# trx-mainboard.net
KiCad netlist of a schematic drawn in EAGLE
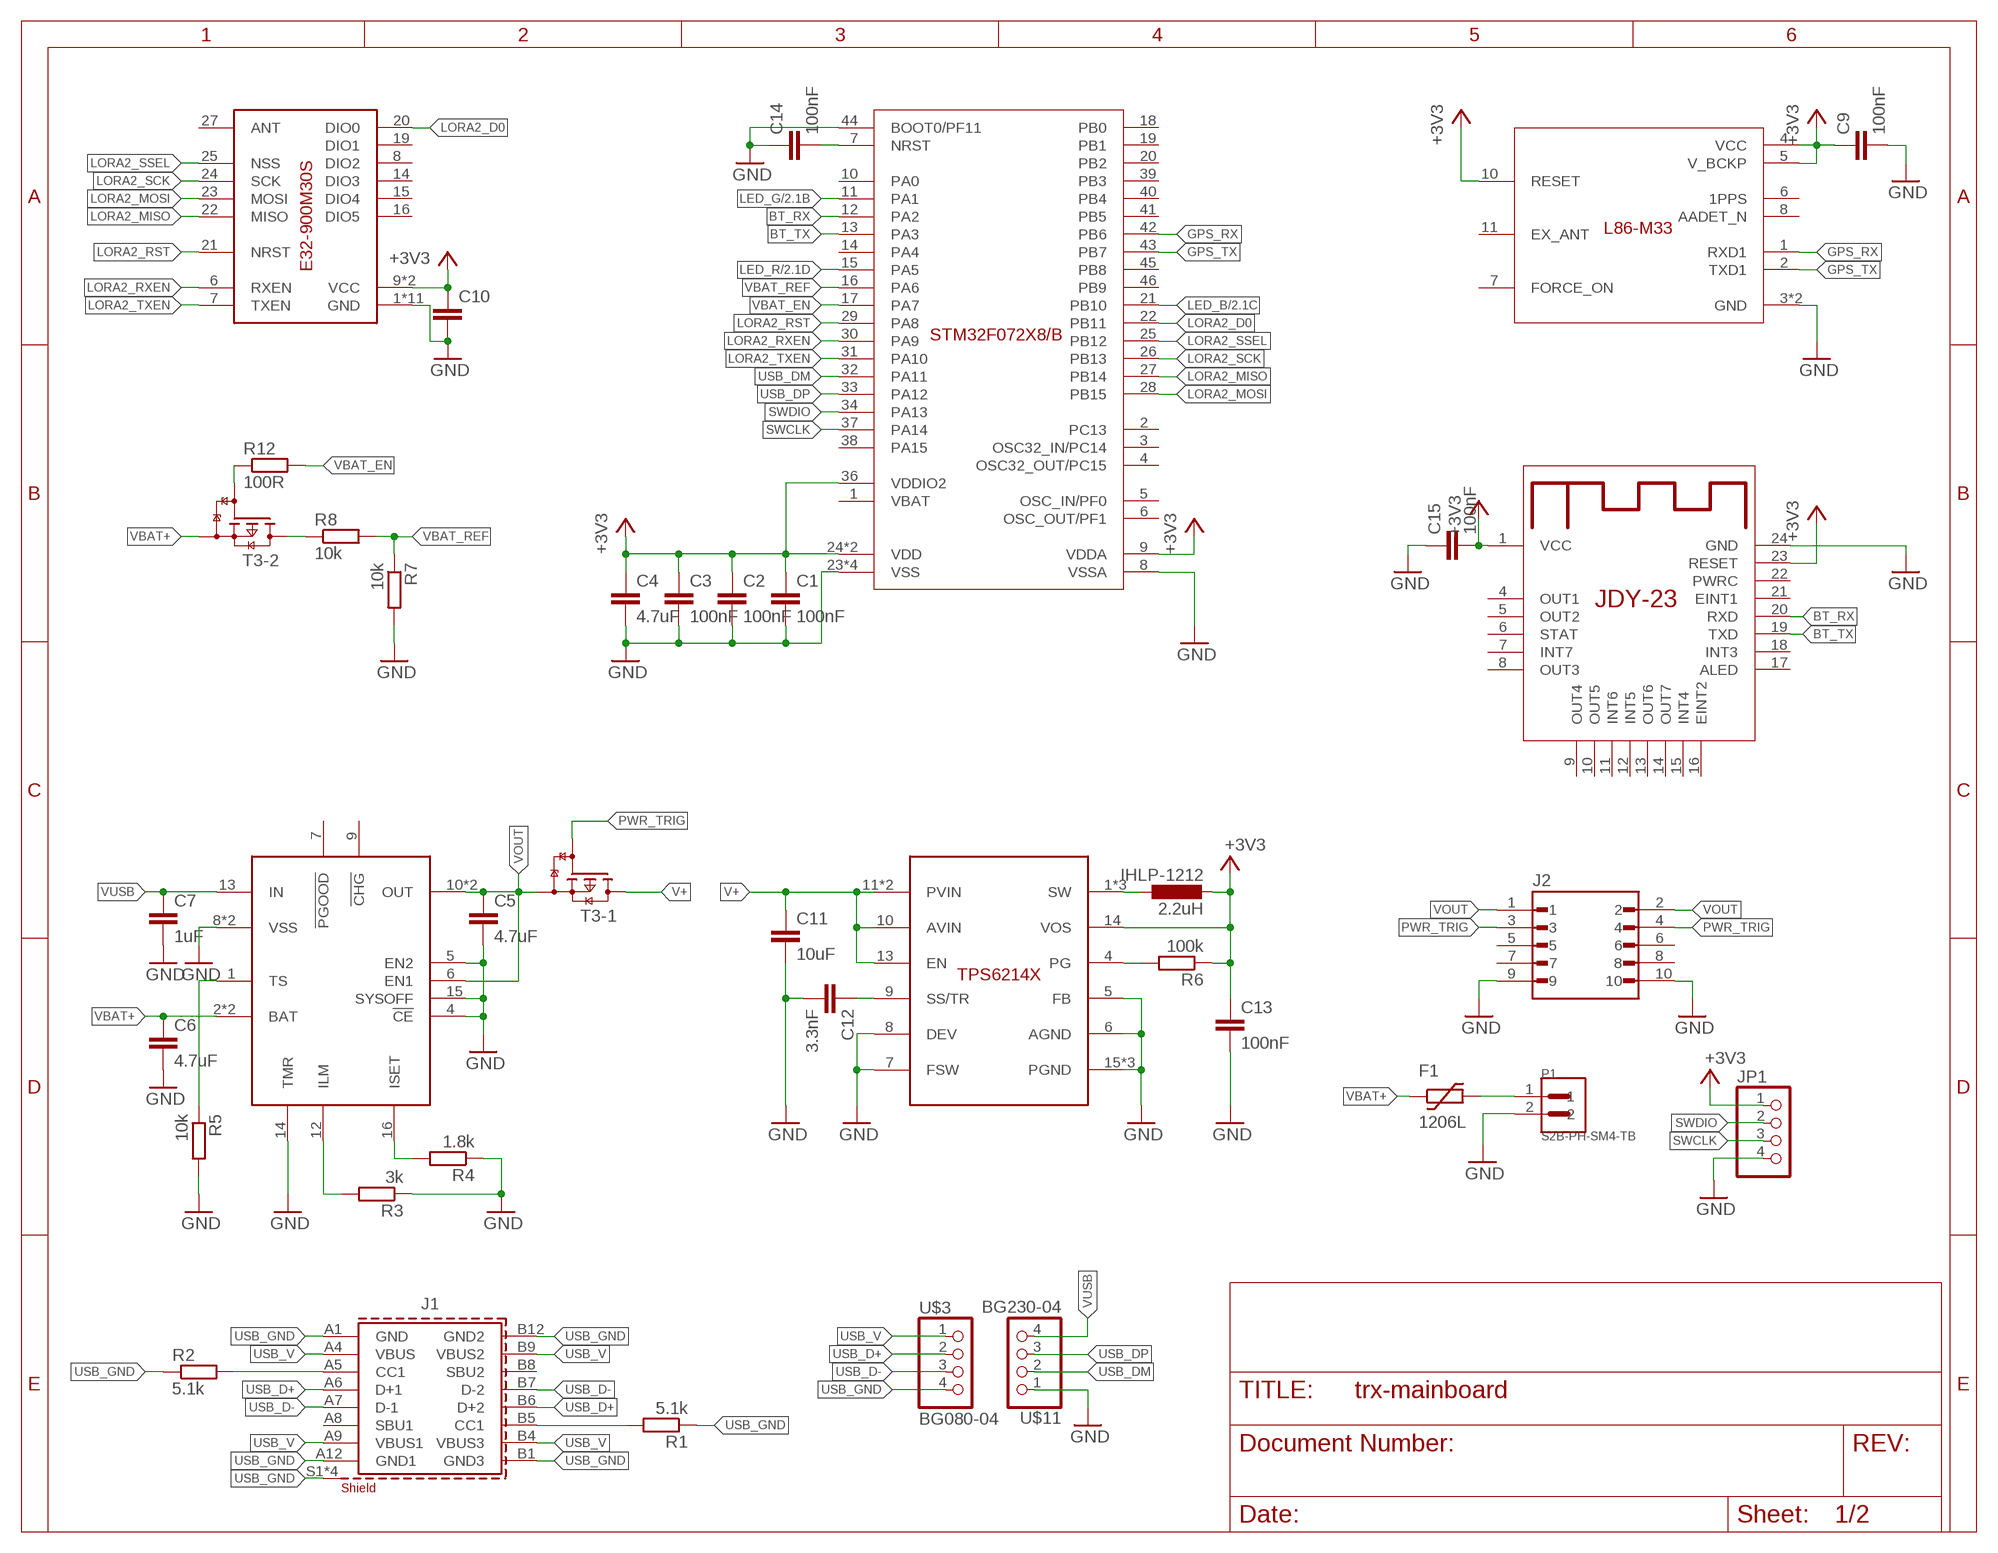
[diagram p0: schematic, sheet 1]
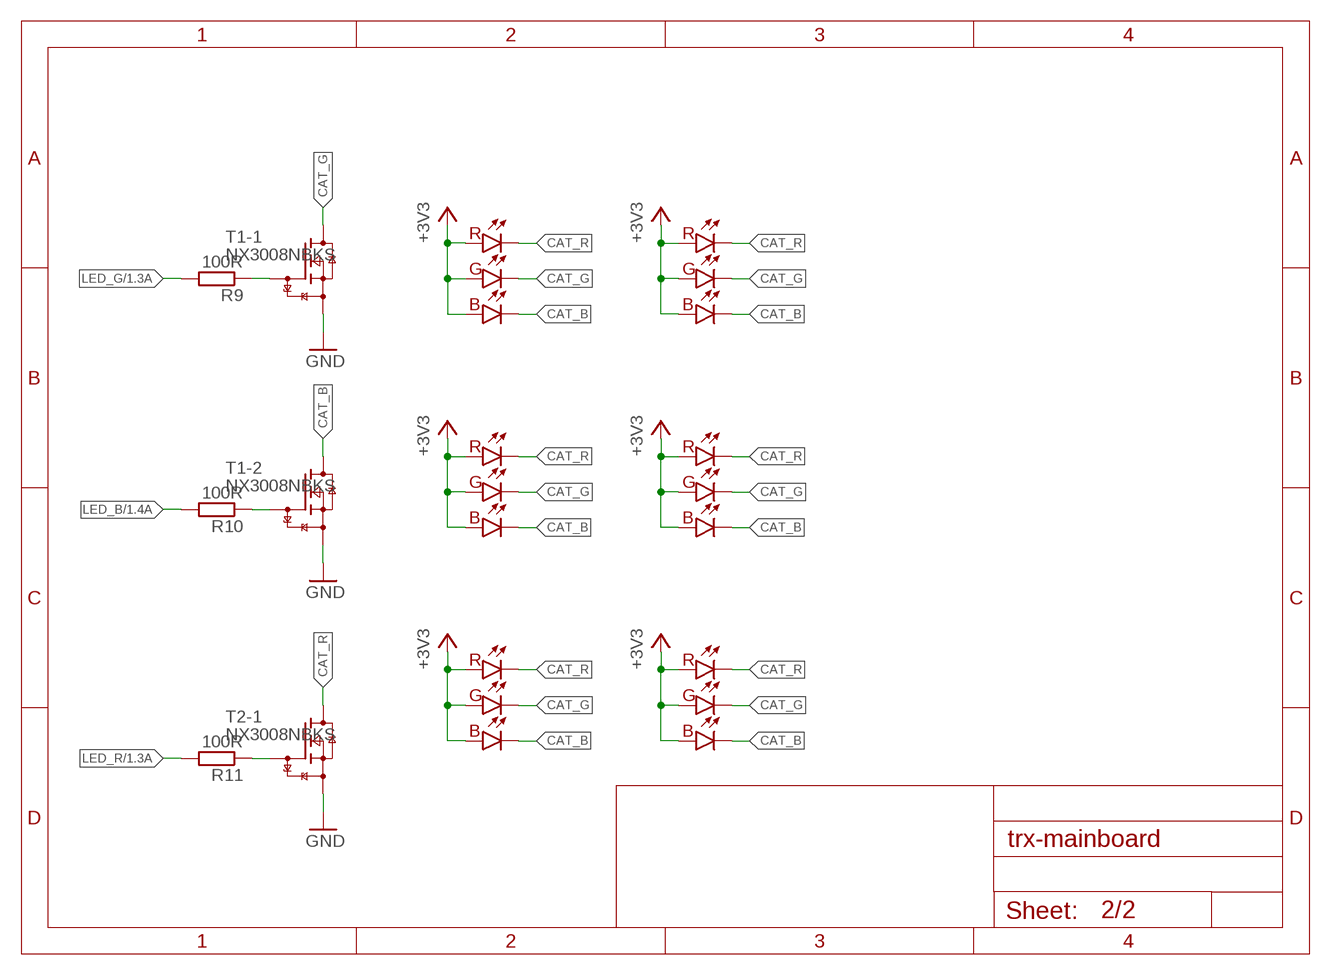
[diagram p1: schematic, sheet 2]

(export (version "E")
  (design (tool "Eeschema 10.0.6"))
  (components
    (comp (ref "C1")
      (value "100nF")
      (footprint "eagle-import:C0805")
      (libsource (lib "eagle-import") (part "C-EUC0805"))
    )
    (comp (ref "C2")
      (value "100nF")
      (footprint "eagle-import:C0805")
      (libsource (lib "eagle-import") (part "C-EUC0805"))
    )
    (comp (ref "C3")
      (value "100nF")
      (footprint "eagle-import:C0805")
      (libsource (lib "eagle-import") (part "C-EUC0805"))
    )
    (comp (ref "C4")
      (value "4.7uF")
      (footprint "eagle-import:C0805")
      (libsource (lib "eagle-import") (part "C-EUC0805"))
    )
    (comp (ref "C5")
      (value "4.7uF")
      (footprint "eagle-import:C0805")
      (libsource (lib "eagle-import") (part "C-EUC0805"))
    )
    (comp (ref "C6")
      (value "4.7uF")
      (footprint "eagle-import:C0805")
      (libsource (lib "eagle-import") (part "C-EUC0805"))
    )
    (comp (ref "C7")
      (value "1uF")
      (footprint "eagle-import:C0805")
      (libsource (lib "eagle-import") (part "C-EUC0805"))
    )
    (comp (ref "C9")
      (value "100nF")
      (footprint "eagle-import:C0805")
      (libsource (lib "eagle-import") (part "C-EUC0805"))
    )
    (comp (ref "C10")
      (value "4.7uF")
      (footprint "eagle-import:C0805")
      (libsource (lib "eagle-import") (part "C-EUC0805"))
    )
    (comp (ref "C11")
      (value "10uF")
      (footprint "eagle-import:C0805")
      (libsource (lib "eagle-import") (part "C-EUC0805"))
    )
    (comp (ref "C12")
      (value "3.3nF")
      (footprint "eagle-import:C0805")
      (libsource (lib "eagle-import") (part "C-EUC0805"))
    )
    (comp (ref "C13")
      (value "100nF")
      (footprint "eagle-import:C0805")
      (libsource (lib "eagle-import") (part "C-EUC0805"))
    )
    (comp (ref "C14")
      (value "100nF")
      (footprint "eagle-import:C0805")
      (libsource (lib "eagle-import") (part "C-EUC0805"))
    )
    (comp (ref "C15")
      (value "100nF")
      (footprint "eagle-import:C0805")
      (libsource (lib "eagle-import") (part "C-EUC0805"))
    )
    (comp (ref "F1")
      (value "1206L")
      (footprint "eagle-import:1206L")
      (libsource (lib "eagle-import") (part "1206L"))
    )
    (comp (ref "J1")
      (value "629722000214")
      (footprint "eagle-import:629722000214")
      (libsource (lib "eagle-import") (part "629722000214"))
    )
    (comp (ref "J2")
      (value "DF12NB(3.0)-10DP-0.5V")
      (footprint "eagle-import:HRS_DF12NB(3.0)-10DP-0.5V")
      (fields (field (name "MF") "Hirose") (field (name "MP") "DF12NB(3.0)-10DP-0.5V(51)"))
      (libsource (lib "eagle-import") (part "DF12NB(3.0)-10DP-0.5V"))
    )
    (comp (ref "JP1")
      (value "PINHD-1X04_2.54-SMD")
      (footprint "eagle-import:1X04SMD")
      (libsource (lib "eagle-import") (part "PINHD-1X04_2.54-SMD"))
    )
    (comp (ref "P1")
      (value "S2B-PH-SM4-TB")
      (footprint "eagle-import:JST_S2B-PH-SM4-TB")
      (fields (field (name "MF") "JST Sales"))
      (libsource (lib "eagle-import") (part "S2B-PH-SM4-TB"))
    )
    (comp (ref "R1")
      (value "5.1k")
      (footprint "eagle-import:R0805")
      (libsource (lib "eagle-import") (part "R-EU_R0805"))
    )
    (comp (ref "R2")
      (value "5.1k")
      (footprint "eagle-import:R0805")
      (libsource (lib "eagle-import") (part "R-EU_R0805"))
    )
    (comp (ref "R3")
      (value "3k")
      (footprint "eagle-import:R0805")
      (libsource (lib "eagle-import") (part "R-EU_R0805"))
    )
    (comp (ref "R4")
      (value "1.8k")
      (footprint "eagle-import:R0805")
      (libsource (lib "eagle-import") (part "R-EU_R0805"))
    )
    (comp (ref "R5")
      (value "10k")
      (footprint "eagle-import:R0805")
      (libsource (lib "eagle-import") (part "R-EU_R0805"))
    )
    (comp (ref "R6")
      (value "100k")
      (footprint "eagle-import:R0805")
      (libsource (lib "eagle-import") (part "R-EU_R0805"))
    )
    (comp (ref "R7")
      (value "10k")
      (footprint "eagle-import:R0805")
      (libsource (lib "eagle-import") (part "R-EU_R0805"))
    )
    (comp (ref "R8")
      (value "10k")
      (footprint "eagle-import:R0805")
      (libsource (lib "eagle-import") (part "R-EU_R0805"))
    )
    (comp (ref "R12")
      (value "100R")
      (footprint "eagle-import:R0805")
      (libsource (lib "eagle-import") (part "R-EU_R0805"))
    )
    (comp (ref "T3")
      (value "NX3008PBKS")
      (footprint "eagle-import:SOT363")
      (libsource (lib "eagle-import") (part "NX3008PBKS"))
    )
    (comp (ref "U$1")
      (value "L86-M33")
      (footprint "eagle-import:L86-M33")
      (libsource (lib "eagle-import") (part "L86-M33"))
    )
    (comp (ref "U$2")
      (value "TPS6214X")
      (footprint "eagle-import:VQFN16-3X3")
      (libsource (lib "eagle-import") (part "TPS6214X"))
    )
    (comp (ref "U$3")
      (value "BG080-04")
      (footprint "eagle-import:P-1X4_90-2.54X1.50MMX2.54MM-SMT")
      (libsource (lib "eagle-import") (part "BG080-04"))
    )
    (comp (ref "U$4")
      (value "IHLP-1212")
      (footprint "eagle-import:1212BZ")
      (libsource (lib "eagle-import") (part "IHLP-1212"))
    )
    (comp (ref "U$5")
      (value "JDY-23")
      (footprint "eagle-import:JDY-23")
      (libsource (lib "eagle-import") (part "JDY-23"))
    )
    (comp (ref "U$10")
      (value "STM32-F072X8/B-48")
      (footprint "eagle-import:UFQFPN48-7X7")
      (libsource (lib "eagle-import") (part "STM32-F072X8/B-48"))
    )
    (comp (ref "U$11")
      (value "BG230-04")
      (footprint "eagle-import:S-1X4_90-2.54MM-SMT")
      (libsource (lib "eagle-import") (part "BG230-04"))
    )
    (comp (ref "U$14")
      (value "E32-900M30S")
      (footprint "eagle-import:E32-900M30S")
      (libsource (lib "eagle-import") (part "E32-900M30S"))
    )
    (comp (ref "U2")
      (value "BQ2407X")
      (footprint "eagle-import:VQFN16-3X3")
      (libsource (lib "eagle-import") (part "BQ2407X"))
    )
    (comp (ref "R9")
      (value "100R")
      (footprint "eagle-import:R0805")
      (libsource (lib "eagle-import") (part "R-EU_R0805"))
    )
    (comp (ref "R10")
      (value "100R")
      (footprint "eagle-import:R0805")
      (libsource (lib "eagle-import") (part "R-EU_R0805"))
    )
    (comp (ref "R11")
      (value "100R")
      (footprint "eagle-import:R0805")
      (libsource (lib "eagle-import") (part "R-EU_R0805"))
    )
    (comp (ref "T1")
      (value "NX3008NBKS")
      (footprint "eagle-import:SOT363")
      (libsource (lib "eagle-import") (part "NX3008NBKS"))
    )
    (comp (ref "T2")
      (value "NX3008NBKS")
      (footprint "eagle-import:SOT363")
      (libsource (lib "eagle-import") (part "NX3008NBKS"))
    )
    (comp (ref "U$6")
      (value "RGB_LED")
      (footprint "eagle-import:PLCC6")
      (libsource (lib "eagle-import") (part "RGB_LED"))
    )
    (comp (ref "U$7")
      (value "RGB_LED")
      (footprint "eagle-import:PLCC6")
      (libsource (lib "eagle-import") (part "RGB_LED"))
    )
    (comp (ref "U$8")
      (value "RGB_LED")
      (footprint "eagle-import:PLCC6")
      (libsource (lib "eagle-import") (part "RGB_LED"))
    )
    (comp (ref "U$9")
      (value "RGB_LED")
      (footprint "eagle-import:PLCC6")
      (libsource (lib "eagle-import") (part "RGB_LED"))
    )
    (comp (ref "U$12")
      (value "RGB_LED")
      (footprint "eagle-import:PLCC6")
      (libsource (lib "eagle-import") (part "RGB_LED"))
    )
    (comp (ref "U$13")
      (value "RGB_LED")
      (footprint "eagle-import:PLCC6")
      (libsource (lib "eagle-import") (part "RGB_LED"))
    )
  )
  (nets
    (net (code "1") (name "+3V3") (class "Default")
      (node (ref "C1") (pin "1") (pinfunction "1_1") (pintype "passive"))
      (node (ref "C10") (pin "1") (pinfunction "1_1") (pintype "passive"))
      (node (ref "C13") (pin "1") (pinfunction "1_1") (pintype "passive"))
      (node (ref "C15") (pin "2") (pinfunction "2_2") (pintype "passive"))
      (node (ref "C2") (pin "1") (pinfunction "1_1") (pintype "passive"))
      (node (ref "C3") (pin "1") (pinfunction "1_1") (pintype "passive"))
      (node (ref "C4") (pin "1") (pinfunction "1_1") (pintype "passive"))
      (node (ref "C9") (pin "1") (pinfunction "1_1") (pintype "passive"))
      (node (ref "JP1") (pin "1") (pinfunction "1_1") (pintype "passive"))
      (node (ref "R6") (pin "1") (pinfunction "1_1") (pintype "passive"))
      (node (ref "U$1") (pin "10") (pinfunction "RESET_10") (pintype "bidirectional"))
      (node (ref "U$1") (pin "4") (pinfunction "VCC_4") (pintype "bidirectional"))
      (node (ref "U$1") (pin "5") (pinfunction "V_BCKP_5") (pintype "bidirectional"))
      (node (ref "U$10") (pin "24") (pinfunction "VDD_24") (pintype "bidirectional"))
      (node (ref "U$10") (pin "36") (pinfunction "VDDIO2_36") (pintype "bidirectional"))
      (node (ref "U$10") (pin "48") (pinfunction "VDD_48") (pintype "bidirectional"))
      (node (ref "U$10") (pin "9") (pinfunction "VDDA_9") (pintype "bidirectional"))
      (node (ref "U$12") (pin "1") (pinfunction "A.B_1") (pintype "passive"))
      (node (ref "U$12") (pin "3") (pinfunction "A.R_3") (pintype "passive"))
      (node (ref "U$12") (pin "5") (pinfunction "A.G_5") (pintype "passive"))
      (node (ref "U$13") (pin "1") (pinfunction "A.B_1") (pintype "passive"))
      (node (ref "U$13") (pin "3") (pinfunction "A.R_3") (pintype "passive"))
      (node (ref "U$13") (pin "5") (pinfunction "A.G_5") (pintype "passive"))
      (node (ref "U$14") (pin "10") (pinfunction "VCC_10") (pintype "bidirectional"))
      (node (ref "U$14") (pin "9") (pinfunction "VCC_9") (pintype "bidirectional"))
      (node (ref "U$2") (pin "14") (pinfunction "VOS_14") (pintype "bidirectional"))
      (node (ref "U$4") (pin "2") (pinfunction "2_2") (pintype "passive"))
      (node (ref "U$5") (pin "1") (pinfunction "VCC_1") (pintype "bidirectional"))
      (node (ref "U$5") (pin "23") (pinfunction "RESET_23") (pintype "bidirectional"))
      (node (ref "U$6") (pin "1") (pinfunction "A.B_1") (pintype "passive"))
      (node (ref "U$6") (pin "3") (pinfunction "A.R_3") (pintype "passive"))
      (node (ref "U$6") (pin "5") (pinfunction "A.G_5") (pintype "passive"))
      (node (ref "U$7") (pin "1") (pinfunction "A.B_1") (pintype "passive"))
      (node (ref "U$7") (pin "3") (pinfunction "A.R_3") (pintype "passive"))
      (node (ref "U$7") (pin "5") (pinfunction "A.G_5") (pintype "passive"))
      (node (ref "U$8") (pin "1") (pinfunction "A.B_1") (pintype "passive"))
      (node (ref "U$8") (pin "3") (pinfunction "A.R_3") (pintype "passive"))
      (node (ref "U$8") (pin "5") (pinfunction "A.G_5") (pintype "passive"))
      (node (ref "U$9") (pin "1") (pinfunction "A.B_1") (pintype "passive"))
      (node (ref "U$9") (pin "3") (pinfunction "A.R_3") (pintype "passive"))
      (node (ref "U$9") (pin "5") (pinfunction "A.G_5") (pintype "passive"))
    )
    (net (code "2") (name "BT_RX") (class "Default")
      (node (ref "U$10") (pin "12") (pinfunction "PA2_12") (pintype "bidirectional"))
      (node (ref "U$5") (pin "20") (pinfunction "RXD_20") (pintype "bidirectional"))
    )
    (net (code "3") (name "BT_TX") (class "Default")
      (node (ref "U$10") (pin "13") (pinfunction "PA3_13") (pintype "bidirectional"))
      (node (ref "U$5") (pin "19") (pinfunction "TXD_19") (pintype "bidirectional"))
    )
    (net (code "4") (name "CAT_B") (class "Default")
      (node (ref "T1") (pin "3") (pinfunction "D_3") (pintype "passive"))
      (node (ref "U$12") (pin "2") (pinfunction "C.B_2") (pintype "passive"))
      (node (ref "U$13") (pin "2") (pinfunction "C.B_2") (pintype "passive"))
      (node (ref "U$6") (pin "2") (pinfunction "C.B_2") (pintype "passive"))
      (node (ref "U$7") (pin "2") (pinfunction "C.B_2") (pintype "passive"))
      (node (ref "U$8") (pin "2") (pinfunction "C.B_2") (pintype "passive"))
      (node (ref "U$9") (pin "2") (pinfunction "C.B_2") (pintype "passive"))
    )
    (net (code "5") (name "CAT_G") (class "Default")
      (node (ref "T1") (pin "6") (pinfunction "D_6") (pintype "passive"))
      (node (ref "U$12") (pin "6") (pinfunction "C.G_6") (pintype "passive"))
      (node (ref "U$13") (pin "6") (pinfunction "C.G_6") (pintype "passive"))
      (node (ref "U$6") (pin "6") (pinfunction "C.G_6") (pintype "passive"))
      (node (ref "U$7") (pin "6") (pinfunction "C.G_6") (pintype "passive"))
      (node (ref "U$8") (pin "6") (pinfunction "C.G_6") (pintype "passive"))
      (node (ref "U$9") (pin "6") (pinfunction "C.G_6") (pintype "passive"))
    )
    (net (code "6") (name "CAT_R") (class "Default")
      (node (ref "T2") (pin "6") (pinfunction "D_6") (pintype "passive"))
      (node (ref "U$12") (pin "4") (pinfunction "C.R_4") (pintype "passive"))
      (node (ref "U$13") (pin "4") (pinfunction "C.R_4") (pintype "passive"))
      (node (ref "U$6") (pin "4") (pinfunction "C.R_4") (pintype "passive"))
      (node (ref "U$7") (pin "4") (pinfunction "C.R_4") (pintype "passive"))
      (node (ref "U$8") (pin "4") (pinfunction "C.R_4") (pintype "passive"))
      (node (ref "U$9") (pin "4") (pinfunction "C.R_4") (pintype "passive"))
    )
    (net (code "7") (name "GND") (class "Default")
      (node (ref "C1") (pin "2") (pinfunction "2_2") (pintype "passive"))
      (node (ref "C10") (pin "2") (pinfunction "2_2") (pintype "passive"))
      (node (ref "C11") (pin "2") (pinfunction "2_2") (pintype "passive"))
      (node (ref "C12") (pin "2") (pinfunction "2_2") (pintype "passive"))
      (node (ref "C13") (pin "2") (pinfunction "2_2") (pintype "passive"))
      (node (ref "C14") (pin "1") (pinfunction "1_1") (pintype "passive"))
      (node (ref "C15") (pin "1") (pinfunction "1_1") (pintype "passive"))
      (node (ref "C2") (pin "2") (pinfunction "2_2") (pintype "passive"))
      (node (ref "C3") (pin "2") (pinfunction "2_2") (pintype "passive"))
      (node (ref "C4") (pin "2") (pinfunction "2_2") (pintype "passive"))
      (node (ref "C5") (pin "2") (pinfunction "2_2") (pintype "passive"))
      (node (ref "C6") (pin "2") (pinfunction "2_2") (pintype "passive"))
      (node (ref "C7") (pin "2") (pinfunction "2_2") (pintype "passive"))
      (node (ref "C9") (pin "2") (pinfunction "2_2") (pintype "passive"))
      (node (ref "J2") (pin "10") (pinfunction "10_10") (pintype "passive"))
      (node (ref "J2") (pin "9") (pinfunction "9_9") (pintype "passive"))
      (node (ref "JP1") (pin "4") (pinfunction "4_4") (pintype "passive"))
      (node (ref "P1") (pin "2") (pinfunction "2_2") (pintype "passive"))
      (node (ref "R3") (pin "1") (pinfunction "1_1") (pintype "passive"))
      (node (ref "R4") (pin "1") (pinfunction "1_1") (pintype "passive"))
      (node (ref "R5") (pin "2") (pinfunction "2_2") (pintype "passive"))
      (node (ref "R7") (pin "2") (pinfunction "2_2") (pintype "passive"))
      (node (ref "T1") (pin "1") (pinfunction "S_1") (pintype "passive"))
      (node (ref "T1") (pin "4") (pinfunction "S_4") (pintype "passive"))
      (node (ref "T2") (pin "1") (pinfunction "S_1") (pintype "passive"))
      (node (ref "U$1") (pin "12") (pinfunction "GND_12") (pintype "bidirectional"))
      (node (ref "U$1") (pin "3") (pinfunction "GND_3") (pintype "bidirectional"))
      (node (ref "U$10") (pin "23") (pinfunction "VSS_23") (pintype "bidirectional"))
      (node (ref "U$10") (pin "35") (pinfunction "VSS_35") (pintype "bidirectional"))
      (node (ref "U$10") (pin "44") (pinfunction "BOOT0/PF11_44") (pintype "bidirectional"))
      (node (ref "U$10") (pin "47") (pinfunction "VSS_47") (pintype "bidirectional"))
      (node (ref "U$10") (pin "8") (pinfunction "VSSA_8") (pintype "bidirectional"))
      (node (ref "U$10") (pin "P$49") (pinfunction "VSS_P$49") (pintype "bidirectional"))
      (node (ref "U$11") (pin "1") (pinfunction "1_1") (pintype "passive"))
      (node (ref "U$14") (pin "1") (pinfunction "GND_1") (pintype "bidirectional"))
      (node (ref "U$14") (pin "11") (pinfunction "GND_11") (pintype "bidirectional"))
      (node (ref "U$14") (pin "12") (pinfunction "GND_12") (pintype "bidirectional"))
      (node (ref "U$14") (pin "17") (pinfunction "GND_17") (pintype "bidirectional"))
      (node (ref "U$14") (pin "18") (pinfunction "GND_18") (pintype "bidirectional"))
      (node (ref "U$14") (pin "2") (pinfunction "GND_2") (pintype "bidirectional"))
      (node (ref "U$14") (pin "26") (pinfunction "GND_26") (pintype "bidirectional"))
      (node (ref "U$14") (pin "28") (pinfunction "GND_28") (pintype "bidirectional"))
      (node (ref "U$14") (pin "3") (pinfunction "GND_3") (pintype "bidirectional"))
      (node (ref "U$14") (pin "4") (pinfunction "GND_4") (pintype "bidirectional"))
      (node (ref "U$14") (pin "5") (pinfunction "GND_5") (pintype "bidirectional"))
      (node (ref "U$2") (pin "15") (pinfunction "PGND_15") (pintype "bidirectional"))
      (node (ref "U$2") (pin "16") (pinfunction "PGND_16") (pintype "bidirectional"))
      (node (ref "U$2") (pin "17") (pinfunction "PGND_17") (pintype "bidirectional"))
      (node (ref "U$2") (pin "5") (pinfunction "FB_5") (pintype "bidirectional"))
      (node (ref "U$2") (pin "6") (pinfunction "AGND_6") (pintype "bidirectional"))
      (node (ref "U$2") (pin "7") (pinfunction "FSW_7") (pintype "bidirectional"))
      (node (ref "U$2") (pin "8") (pinfunction "DEV_8") (pintype "bidirectional"))
      (node (ref "U$5") (pin "24") (pinfunction "GND_24") (pintype "bidirectional"))
      (node (ref "U2") (pin "14") (pinfunction "TMR_14") (pintype "bidirectional"))
      (node (ref "U2") (pin "15") (pinfunction "SYSOFF_15") (pintype "bidirectional"))
      (node (ref "U2") (pin "17") (pinfunction "VSS_17") (pintype "bidirectional"))
      (node (ref "U2") (pin "4") (pinfunction "~{CE}_4") (pintype "bidirectional"))
      (node (ref "U2") (pin "5") (pinfunction "EN2_5") (pintype "bidirectional"))
      (node (ref "U2") (pin "8") (pinfunction "VSS_8") (pintype "bidirectional"))
    )
    (net (code "8") (name "GPS_RX") (class "Default")
      (node (ref "U$1") (pin "1") (pinfunction "RXD1_1") (pintype "bidirectional"))
      (node (ref "U$10") (pin "42") (pinfunction "PB6_42") (pintype "bidirectional"))
    )
    (net (code "9") (name "GPS_TX") (class "Default")
      (node (ref "U$1") (pin "2") (pinfunction "TXD1_2") (pintype "bidirectional"))
      (node (ref "U$10") (pin "43") (pinfunction "PB7_43") (pintype "bidirectional"))
    )
    (net (code "10") (name "LED_B") (class "Default")
      (node (ref "R10") (pin "2") (pinfunction "2_2") (pintype "passive"))
      (node (ref "U$10") (pin "21") (pinfunction "PB10_21") (pintype "bidirectional"))
    )
    (net (code "11") (name "LED_G") (class "Default")
      (node (ref "R9") (pin "2") (pinfunction "2_2") (pintype "passive"))
      (node (ref "U$10") (pin "11") (pinfunction "PA1_11") (pintype "bidirectional"))
    )
    (net (code "12") (name "LED_R") (class "Default")
      (node (ref "R11") (pin "2") (pinfunction "2_2") (pintype "passive"))
      (node (ref "U$10") (pin "15") (pinfunction "PA5_15") (pintype "bidirectional"))
    )
    (net (code "13") (name "LORA2_D0") (class "Default")
      (node (ref "U$10") (pin "22") (pinfunction "PB11_22") (pintype "bidirectional"))
      (node (ref "U$14") (pin "20") (pinfunction "DIO0_20") (pintype "bidirectional"))
    )
    (net (code "14") (name "LORA2_MISO") (class "Default")
      (node (ref "U$10") (pin "27") (pinfunction "PB14_27") (pintype "bidirectional"))
      (node (ref "U$14") (pin "22") (pinfunction "MISO_22") (pintype "bidirectional"))
    )
    (net (code "15") (name "LORA2_MOSI") (class "Default")
      (node (ref "U$10") (pin "28") (pinfunction "PB15_28") (pintype "bidirectional"))
      (node (ref "U$14") (pin "23") (pinfunction "MOSI_23") (pintype "bidirectional"))
    )
    (net (code "16") (name "LORA2_RST") (class "Default")
      (node (ref "U$10") (pin "29") (pinfunction "PA8_29") (pintype "bidirectional"))
      (node (ref "U$14") (pin "21") (pinfunction "NRST_21") (pintype "bidirectional"))
    )
    (net (code "17") (name "LORA2_RXEN") (class "Default")
      (node (ref "U$10") (pin "30") (pinfunction "PA9_30") (pintype "bidirectional"))
      (node (ref "U$14") (pin "6") (pinfunction "RXEN_6") (pintype "bidirectional"))
    )
    (net (code "18") (name "LORA2_SCK") (class "Default")
      (node (ref "U$10") (pin "26") (pinfunction "PB13_26") (pintype "bidirectional"))
      (node (ref "U$14") (pin "24") (pinfunction "SCK_24") (pintype "bidirectional"))
    )
    (net (code "19") (name "LORA2_SSEL") (class "Default")
      (node (ref "U$10") (pin "25") (pinfunction "PB12_25") (pintype "bidirectional"))
      (node (ref "U$14") (pin "25") (pinfunction "NSS_25") (pintype "bidirectional"))
    )
    (net (code "20") (name "LORA2_TXEN") (class "Default")
      (node (ref "U$10") (pin "31") (pinfunction "PA10_31") (pintype "bidirectional"))
      (node (ref "U$14") (pin "7") (pinfunction "TXEN_7") (pintype "bidirectional"))
    )
    (net (code "21") (name "Net-(F1-2)") (class "Default")
      (node (ref "F1") (pin "P$2") (pinfunction "2_P$2") (pintype "passive"))
      (node (ref "P1") (pin "1") (pinfunction "1_1") (pintype "passive"))
    )
    (net (code "22") (name "Net-(J1-CC1-PadA5)") (class "Default")
      (node (ref "J1") (pin "A5") (pinfunction "CC1_A5") (pintype "passive"))
      (node (ref "R2") (pin "2") (pinfunction "2_2") (pintype "passive"))
    )
    (net (code "23") (name "Net-(J1-CC1-PadB5)") (class "Default")
      (node (ref "J1") (pin "B5") (pinfunction "CC1_B5") (pintype "passive"))
      (node (ref "R1") (pin "2") (pinfunction "2_2") (pintype "passive"))
    )
    (net (code "24") (name "Net-(T1A-G)") (class "Default")
      (node (ref "R9") (pin "1") (pinfunction "1_1") (pintype "passive"))
      (node (ref "T1") (pin "2") (pinfunction "G_2") (pintype "passive"))
    )
    (net (code "25") (name "Net-(T1B-G)") (class "Default")
      (node (ref "R10") (pin "1") (pinfunction "1_1") (pintype "passive"))
      (node (ref "T1") (pin "5") (pinfunction "G_5") (pintype "passive"))
    )
    (net (code "26") (name "Net-(T2A-G)") (class "Default")
      (node (ref "R11") (pin "1") (pinfunction "1_1") (pintype "passive"))
      (node (ref "T2") (pin "2") (pinfunction "G_2") (pintype "passive"))
    )
    (net (code "27") (name "Net-(T3B-D)") (class "Default")
      (node (ref "R8") (pin "1") (pinfunction "1_1") (pintype "passive"))
      (node (ref "T3") (pin "3") (pinfunction "D_3") (pintype "passive"))
    )
    (net (code "28") (name "Net-(T3B-G)") (class "Default")
      (node (ref "R12") (pin "1") (pinfunction "1_1") (pintype "passive"))
      (node (ref "T3") (pin "5") (pinfunction "G_5") (pintype "passive"))
    )
    (net (code "29") (name "Net-(U$2-PG)") (class "Default")
      (node (ref "R6") (pin "2") (pinfunction "2_2") (pintype "passive"))
      (node (ref "U$2") (pin "4") (pinfunction "PG_4") (pintype "bidirectional"))
    )
    (net (code "30") (name "Net-(U$2-SS{slash}TR)") (class "Default")
      (node (ref "C12") (pin "1") (pinfunction "1_1") (pintype "passive"))
      (node (ref "U$2") (pin "9") (pinfunction "SS/TR_9") (pintype "bidirectional"))
    )
    (net (code "31") (name "Net-(U$2-SW-Pad1)") (class "Default")
      (node (ref "U$2") (pin "1") (pinfunction "SW_1") (pintype "bidirectional"))
      (node (ref "U$2") (pin "2") (pinfunction "SW_2") (pintype "bidirectional"))
      (node (ref "U$2") (pin "3") (pinfunction "SW_3") (pintype "bidirectional"))
      (node (ref "U$4") (pin "1") (pinfunction "1_1") (pintype "passive"))
    )
    (net (code "32") (name "Net-(U$10-NRST)") (class "Default")
      (node (ref "C14") (pin "2") (pinfunction "2_2") (pintype "passive"))
      (node (ref "U$10") (pin "7") (pinfunction "NRST_7") (pintype "bidirectional"))
    )
    (net (code "33") (name "Net-(U2-ILM)") (class "Default")
      (node (ref "R3") (pin "2") (pinfunction "2_2") (pintype "passive"))
      (node (ref "U2") (pin "12") (pinfunction "ILM_12") (pintype "bidirectional"))
    )
    (net (code "34") (name "Net-(U2-ISET)") (class "Default")
      (node (ref "R4") (pin "2") (pinfunction "2_2") (pintype "passive"))
      (node (ref "U2") (pin "16") (pinfunction "ISET_16") (pintype "bidirectional"))
    )
    (net (code "35") (name "Net-(U2-TS)") (class "Default")
      (node (ref "R5") (pin "1") (pinfunction "1_1") (pintype "passive"))
      (node (ref "U2") (pin "1") (pinfunction "TS_1") (pintype "bidirectional"))
    )
    (net (code "36") (name "PWR_TRIG") (class "Default")
      (node (ref "J2") (pin "3") (pinfunction "3_3") (pintype "passive"))
      (node (ref "J2") (pin "4") (pinfunction "4_4") (pintype "passive"))
      (node (ref "T3") (pin "2") (pinfunction "G_2") (pintype "passive"))
    )
    (net (code "37") (name "SWCLK") (class "Default")
      (node (ref "JP1") (pin "3") (pinfunction "3_3") (pintype "passive"))
      (node (ref "U$10") (pin "37") (pinfunction "PA14_37") (pintype "bidirectional"))
    )
    (net (code "38") (name "SWDIO") (class "Default")
      (node (ref "JP1") (pin "2") (pinfunction "2_2") (pintype "passive"))
      (node (ref "U$10") (pin "34") (pinfunction "PA13_34") (pintype "bidirectional"))
    )
    (net (code "39") (name "USB_D+") (class "Default")
      (node (ref "J1") (pin "A6") (pinfunction "D+1_A6") (pintype "passive"))
      (node (ref "J1") (pin "B6") (pinfunction "D+2_B6") (pintype "passive"))
      (node (ref "U$3") (pin "2") (pinfunction "2_2") (pintype "passive"))
    )
    (net (code "40") (name "USB_D-") (class "Default")
      (node (ref "J1") (pin "A7") (pinfunction "D-1_A7") (pintype "passive"))
      (node (ref "J1") (pin "B7") (pinfunction "D-2_B7") (pintype "passive"))
      (node (ref "U$3") (pin "3") (pinfunction "3_3") (pintype "passive"))
    )
    (net (code "41") (name "USB_DM") (class "Default")
      (node (ref "U$10") (pin "32") (pinfunction "PA11_32") (pintype "bidirectional"))
      (node (ref "U$11") (pin "2") (pinfunction "2_2") (pintype "passive"))
    )
    (net (code "42") (name "USB_DP") (class "Default")
      (node (ref "U$10") (pin "33") (pinfunction "PA12_33") (pintype "bidirectional"))
      (node (ref "U$11") (pin "3") (pinfunction "3_3") (pintype "passive"))
    )
    (net (code "43") (name "USB_GND") (class "Default")
      (node (ref "J1") (pin "A1") (pinfunction "GND_A1") (pintype "passive"))
      (node (ref "J1") (pin "A12") (pinfunction "GND1_A12") (pintype "passive"))
      (node (ref "J1") (pin "B1") (pinfunction "GND3_B1") (pintype "passive"))
      (node (ref "J1") (pin "B12") (pinfunction "GND2_B12") (pintype "passive"))
      (node (ref "J1") (pin "S1") (pinfunction "SHIELD_S1") (pintype "passive"))
      (node (ref "J1") (pin "S2") (pinfunction "SHIELD_S2") (pintype "passive"))
      (node (ref "J1") (pin "S3") (pinfunction "SHIELD_S3") (pintype "passive"))
      (node (ref "J1") (pin "S4") (pinfunction "SHIELD_S4") (pintype "passive"))
      (node (ref "R1") (pin "1") (pinfunction "1_1") (pintype "passive"))
      (node (ref "R2") (pin "1") (pinfunction "1_1") (pintype "passive"))
      (node (ref "U$3") (pin "4") (pinfunction "4_4") (pintype "passive"))
    )
    (net (code "44") (name "USB_V") (class "Default")
      (node (ref "J1") (pin "A4") (pinfunction "VBUS_A4") (pintype "passive"))
      (node (ref "J1") (pin "A9") (pinfunction "VBUS1_A9") (pintype "passive"))
      (node (ref "J1") (pin "B4") (pinfunction "VBUS3_B4") (pintype "passive"))
      (node (ref "J1") (pin "B9") (pinfunction "VBUS2_B9") (pintype "passive"))
      (node (ref "U$3") (pin "1") (pinfunction "1_1") (pintype "passive"))
    )
    (net (code "45") (name "V+") (class "Default")
      (node (ref "C11") (pin "1") (pinfunction "1_1") (pintype "passive"))
      (node (ref "T3") (pin "6") (pinfunction "D_6") (pintype "passive"))
      (node (ref "U$2") (pin "10") (pinfunction "AVIN_10") (pintype "bidirectional"))
      (node (ref "U$2") (pin "11") (pinfunction "PVIN_11") (pintype "bidirectional"))
      (node (ref "U$2") (pin "12") (pinfunction "PVIN_12") (pintype "bidirectional"))
      (node (ref "U$2") (pin "13") (pinfunction "EN_13") (pintype "bidirectional"))
    )
    (net (code "46") (name "VBAT+") (class "Default")
      (node (ref "C6") (pin "1") (pinfunction "1_1") (pintype "passive"))
      (node (ref "F1") (pin "P$1") (pinfunction "1_P$1") (pintype "passive"))
      (node (ref "T3") (pin "4") (pinfunction "S_4") (pintype "passive"))
      (node (ref "U2") (pin "2") (pinfunction "BAT_2") (pintype "bidirectional"))
      (node (ref "U2") (pin "3") (pinfunction "BAT_3") (pintype "bidirectional"))
    )
    (net (code "47") (name "VBAT_EN") (class "Default")
      (node (ref "R12") (pin "2") (pinfunction "2_2") (pintype "passive"))
      (node (ref "U$10") (pin "17") (pinfunction "PA7_17") (pintype "bidirectional"))
    )
    (net (code "48") (name "VBAT_REF") (class "Default")
      (node (ref "R7") (pin "1") (pinfunction "1_1") (pintype "passive"))
      (node (ref "R8") (pin "2") (pinfunction "2_2") (pintype "passive"))
      (node (ref "U$10") (pin "16") (pinfunction "PA6_16") (pintype "bidirectional"))
    )
    (net (code "49") (name "VOUT") (class "Default")
      (node (ref "C5") (pin "1") (pinfunction "1_1") (pintype "passive"))
      (node (ref "J2") (pin "1") (pinfunction "1_1") (pintype "passive"))
      (node (ref "J2") (pin "2") (pinfunction "2_2") (pintype "passive"))
      (node (ref "T3") (pin "1") (pinfunction "S_1") (pintype "passive"))
      (node (ref "U2") (pin "10") (pinfunction "OUT_10") (pintype "bidirectional"))
      (node (ref "U2") (pin "11") (pinfunction "OUT_11") (pintype "bidirectional"))
      (node (ref "U2") (pin "6") (pinfunction "EN1_6") (pintype "bidirectional"))
    )
    (net (code "50") (name "VUSB") (class "Default")
      (node (ref "C7") (pin "1") (pinfunction "1_1") (pintype "passive"))
      (node (ref "U$11") (pin "4") (pinfunction "4_4") (pintype "passive"))
      (node (ref "U2") (pin "13") (pinfunction "IN_13") (pintype "bidirectional"))
    )
    (net (code "51") (name "unconnected-(J1-SBU1-PadA8)") (class "Default")
      (node (ref "J1") (pin "A8") (pinfunction "SBU1_A8") (pintype "passive"))
    )
    (net (code "52") (name "unconnected-(J1-SBU2-PadB8)") (class "Default")
      (node (ref "J1") (pin "B8") (pinfunction "SBU2_B8") (pintype "passive"))
    )
    (net (code "53") (name "unconnected-(J2-Pad5)") (class "Default")
      (node (ref "J2") (pin "5") (pinfunction "5_5") (pintype "passive"))
    )
    (net (code "54") (name "unconnected-(J2-Pad6)") (class "Default")
      (node (ref "J2") (pin "6") (pinfunction "6_6") (pintype "passive"))
    )
    (net (code "55") (name "unconnected-(J2-Pad7)") (class "Default")
      (node (ref "J2") (pin "7") (pinfunction "7_7") (pintype "passive"))
    )
    (net (code "56") (name "unconnected-(J2-Pad8)") (class "Default")
      (node (ref "J2") (pin "8") (pinfunction "8_8") (pintype "passive"))
    )
    (net (code "57") (name "unconnected-(U$1-1PPS-Pad6)") (class "Default")
      (node (ref "U$1") (pin "6") (pinfunction "1PPS_6") (pintype "bidirectional"))
    )
    (net (code "58") (name "unconnected-(U$1-AADET_N-Pad8)") (class "Default")
      (node (ref "U$1") (pin "8") (pinfunction "AADET_N_8") (pintype "bidirectional"))
    )
    (net (code "59") (name "unconnected-(U$1-EX_ANT-Pad11)") (class "Default")
      (node (ref "U$1") (pin "11") (pinfunction "EX_ANT_11") (pintype "bidirectional"))
    )
    (net (code "60") (name "unconnected-(U$1-FORCE_ON-Pad7)") (class "Default")
      (node (ref "U$1") (pin "7") (pinfunction "FORCE_ON_7") (pintype "bidirectional"))
    )
    (net (code "61") (name "unconnected-(U$5-ALED-Pad17)") (class "Default")
      (node (ref "U$5") (pin "17") (pinfunction "ALED_17") (pintype "bidirectional"))
    )
    (net (code "62") (name "unconnected-(U$5-EINT1-Pad21)") (class "Default")
      (node (ref "U$5") (pin "21") (pinfunction "EINT1_21") (pintype "bidirectional"))
    )
    (net (code "63") (name "unconnected-(U$5-EINT2-Pad16)") (class "Default")
      (node (ref "U$5") (pin "16") (pinfunction "EINT2_16") (pintype "bidirectional"))
    )
    (net (code "64") (name "unconnected-(U$5-INT3-Pad18)") (class "Default")
      (node (ref "U$5") (pin "18") (pinfunction "INT3_18") (pintype "bidirectional"))
    )
    (net (code "65") (name "unconnected-(U$5-INT4-Pad15)") (class "Default")
      (node (ref "U$5") (pin "15") (pinfunction "INT4_15") (pintype "bidirectional"))
    )
    (net (code "66") (name "unconnected-(U$5-INT5-Pad12)") (class "Default")
      (node (ref "U$5") (pin "12") (pinfunction "INT5_12") (pintype "bidirectional"))
    )
    (net (code "67") (name "unconnected-(U$5-INT6-Pad11)") (class "Default")
      (node (ref "U$5") (pin "11") (pinfunction "INT6_11") (pintype "bidirectional"))
    )
    (net (code "68") (name "unconnected-(U$5-INT7-Pad7)") (class "Default")
      (node (ref "U$5") (pin "7") (pinfunction "INT7_7") (pintype "bidirectional"))
    )
    (net (code "69") (name "unconnected-(U$5-OUT1-Pad4)") (class "Default")
      (node (ref "U$5") (pin "4") (pinfunction "OUT1_4") (pintype "bidirectional"))
    )
    (net (code "70") (name "unconnected-(U$5-OUT2-Pad5)") (class "Default")
      (node (ref "U$5") (pin "5") (pinfunction "OUT2_5") (pintype "bidirectional"))
    )
    (net (code "71") (name "unconnected-(U$5-OUT3-Pad8)") (class "Default")
      (node (ref "U$5") (pin "8") (pinfunction "OUT3_8") (pintype "bidirectional"))
    )
    (net (code "72") (name "unconnected-(U$5-OUT4-Pad9)") (class "Default")
      (node (ref "U$5") (pin "9") (pinfunction "OUT4_9") (pintype "bidirectional"))
    )
    (net (code "73") (name "unconnected-(U$5-OUT5-Pad10)") (class "Default")
      (node (ref "U$5") (pin "10") (pinfunction "OUT5_10") (pintype "bidirectional"))
    )
    (net (code "74") (name "unconnected-(U$5-OUT6-Pad13)") (class "Default")
      (node (ref "U$5") (pin "13") (pinfunction "OUT6_13") (pintype "bidirectional"))
    )
    (net (code "75") (name "unconnected-(U$5-OUT7-Pad14)") (class "Default")
      (node (ref "U$5") (pin "14") (pinfunction "OUT7_14") (pintype "bidirectional"))
    )
    (net (code "76") (name "unconnected-(U$5-PWRC-Pad22)") (class "Default")
      (node (ref "U$5") (pin "22") (pinfunction "PWRC_22") (pintype "bidirectional"))
    )
    (net (code "77") (name "unconnected-(U$5-STAT-Pad6)") (class "Default")
      (node (ref "U$5") (pin "6") (pinfunction "STAT_6") (pintype "bidirectional"))
    )
    (net (code "78") (name "unconnected-(U$10-OSC32_IN{slash}PC14-Pad3)") (class "Default")
      (node (ref "U$10") (pin "3") (pinfunction "OSC32_IN/PC14_3") (pintype "bidirectional"))
    )
    (net (code "79") (name "unconnected-(U$10-OSC32_OUT{slash}PC15-Pad4)") (class "Default")
      (node (ref "U$10") (pin "4") (pinfunction "OSC32_OUT/PC15_4") (pintype "bidirectional"))
    )
    (net (code "80") (name "unconnected-(U$10-OSC_IN{slash}PF0-Pad5)") (class "Default")
      (node (ref "U$10") (pin "5") (pinfunction "OSC_IN/PF0_5") (pintype "bidirectional"))
    )
    (net (code "81") (name "unconnected-(U$10-OSC_OUT{slash}PF1-Pad6)") (class "Default")
      (node (ref "U$10") (pin "6") (pinfunction "OSC_OUT/PF1_6") (pintype "bidirectional"))
    )
    (net (code "82") (name "unconnected-(U$10-PA0-Pad10)") (class "Default")
      (node (ref "U$10") (pin "10") (pinfunction "PA0_10") (pintype "bidirectional"))
    )
    (net (code "83") (name "unconnected-(U$10-PA4-Pad14)") (class "Default")
      (node (ref "U$10") (pin "14") (pinfunction "PA4_14") (pintype "bidirectional"))
    )
    (net (code "84") (name "unconnected-(U$10-PA15-Pad38)") (class "Default")
      (node (ref "U$10") (pin "38") (pinfunction "PA15_38") (pintype "bidirectional"))
    )
    (net (code "85") (name "unconnected-(U$10-PB0-Pad18)") (class "Default")
      (node (ref "U$10") (pin "18") (pinfunction "PB0_18") (pintype "bidirectional"))
    )
    (net (code "86") (name "unconnected-(U$10-PB1-Pad19)") (class "Default")
      (node (ref "U$10") (pin "19") (pinfunction "PB1_19") (pintype "bidirectional"))
    )
    (net (code "87") (name "unconnected-(U$10-PB2-Pad20)") (class "Default")
      (node (ref "U$10") (pin "20") (pinfunction "PB2_20") (pintype "bidirectional"))
    )
    (net (code "88") (name "unconnected-(U$10-PB3-Pad39)") (class "Default")
      (node (ref "U$10") (pin "39") (pinfunction "PB3_39") (pintype "bidirectional"))
    )
    (net (code "89") (name "unconnected-(U$10-PB4-Pad40)") (class "Default")
      (node (ref "U$10") (pin "40") (pinfunction "PB4_40") (pintype "bidirectional"))
    )
    (net (code "90") (name "unconnected-(U$10-PB5-Pad41)") (class "Default")
      (node (ref "U$10") (pin "41") (pinfunction "PB5_41") (pintype "bidirectional"))
    )
    (net (code "91") (name "unconnected-(U$10-PB8-Pad45)") (class "Default")
      (node (ref "U$10") (pin "45") (pinfunction "PB8_45") (pintype "bidirectional"))
    )
    (net (code "92") (name "unconnected-(U$10-PB9-Pad46)") (class "Default")
      (node (ref "U$10") (pin "46") (pinfunction "PB9_46") (pintype "bidirectional"))
    )
    (net (code "93") (name "unconnected-(U$10-PC13-Pad2)") (class "Default")
      (node (ref "U$10") (pin "2") (pinfunction "PC13_2") (pintype "bidirectional"))
    )
    (net (code "94") (name "unconnected-(U$10-VBAT-Pad1)") (class "Default")
      (node (ref "U$10") (pin "1") (pinfunction "VBAT_1") (pintype "bidirectional"))
    )
    (net (code "95") (name "unconnected-(U$14-ANT-Pad27)") (class "Default")
      (node (ref "U$14") (pin "27") (pinfunction "ANT_27") (pintype "bidirectional"))
    )
    (net (code "96") (name "unconnected-(U$14-DIO1-Pad19)") (class "Default")
      (node (ref "U$14") (pin "19") (pinfunction "DIO1_19") (pintype "bidirectional"))
    )
    (net (code "97") (name "unconnected-(U$14-DIO2-Pad8)") (class "Default")
      (node (ref "U$14") (pin "8") (pinfunction "DIO2_8") (pintype "bidirectional"))
    )
    (net (code "98") (name "unconnected-(U$14-DIO3-Pad14)") (class "Default")
      (node (ref "U$14") (pin "14") (pinfunction "DIO3_14") (pintype "bidirectional"))
    )
    (net (code "99") (name "unconnected-(U$14-DIO4-Pad15)") (class "Default")
      (node (ref "U$14") (pin "15") (pinfunction "DIO4_15") (pintype "bidirectional"))
    )
    (net (code "100") (name "unconnected-(U$14-DIO5-Pad16)") (class "Default")
      (node (ref "U$14") (pin "16") (pinfunction "DIO5_16") (pintype "bidirectional"))
    )
    (net (code "101") (name "unconnected-(U2-~{CHG}-Pad9)") (class "Default")
      (node (ref "U2") (pin "9") (pinfunction "~{CHG}_9") (pintype "bidirectional"))
    )
    (net (code "102") (name "unconnected-(U2-~{PGOOD}-Pad7)") (class "Default")
      (node (ref "U2") (pin "7") (pinfunction "~{PGOOD}_7") (pintype "bidirectional"))
    )
  )
)
